# reservoir_level_color.net
KiCad netlist of a schematic drawn in Altium Designer
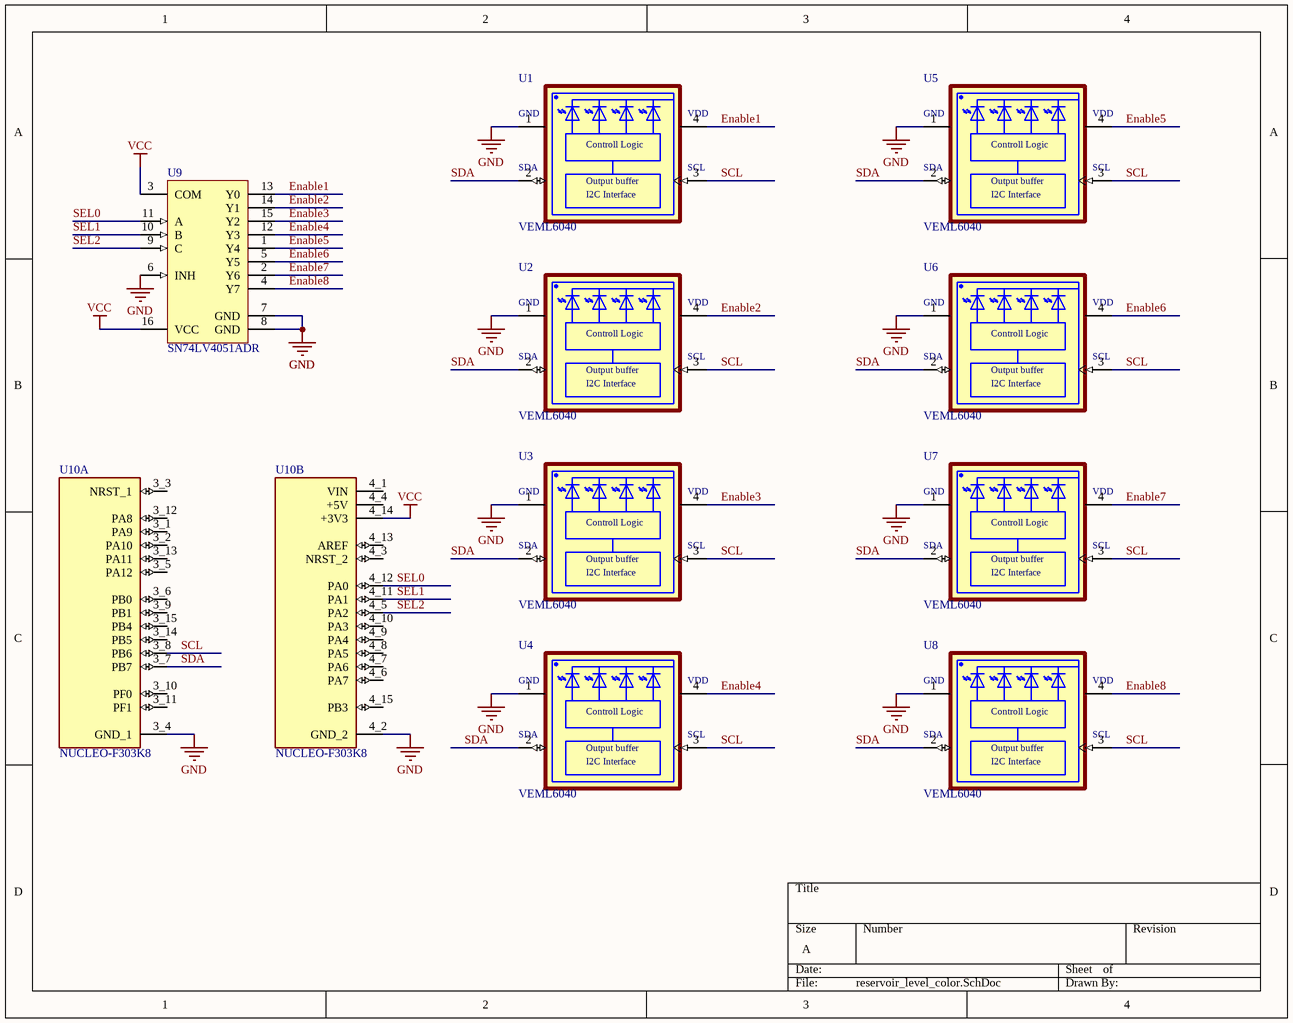
[diagram p0: reservoir_level_color.SchDoc]

(export (version "E")
  (design (tool "Eeschema 10.0.6"))
  (components
    (comp (ref "U1")
      (value "VEML6040")
      (footprint "VEML6040A3OG:VISHAY_VEML6040_1.25X2X1")
      (fields (field (name "MF") "{'manufacturer': u'Vishay'}"))
      (libsource (lib "*") (part "VEML6040"))
    )
    (comp (ref "U2")
      (value "VEML6040")
      (footprint "VEML6040A3OG:VISHAY_VEML6040_1.25X2X1")
      (fields (field (name "MF") "{'manufacturer': u'Vishay'}"))
      (libsource (lib "*") (part "VEML6040"))
    )
    (comp (ref "U3")
      (value "VEML6040")
      (footprint "VEML6040A3OG:VISHAY_VEML6040_1.25X2X1")
      (fields (field (name "MF") "{'manufacturer': u'Vishay'}"))
      (libsource (lib "*") (part "VEML6040"))
    )
    (comp (ref "U4")
      (value "VEML6040")
      (footprint "VEML6040A3OG:VISHAY_VEML6040_1.25X2X1")
      (fields (field (name "MF") "{'manufacturer': u'Vishay'}"))
      (libsource (lib "*") (part "VEML6040"))
    )
    (comp (ref "U5")
      (value "VEML6040")
      (footprint "VEML6040A3OG:VISHAY_VEML6040_1.25X2X1")
      (fields (field (name "MF") "{'manufacturer': u'Vishay'}"))
      (libsource (lib "*") (part "VEML6040"))
    )
    (comp (ref "U6")
      (value "VEML6040")
      (footprint "VEML6040A3OG:VISHAY_VEML6040_1.25X2X1")
      (fields (field (name "MF") "{'manufacturer': u'Vishay'}"))
      (libsource (lib "*") (part "VEML6040"))
    )
    (comp (ref "U7")
      (value "VEML6040")
      (footprint "VEML6040A3OG:VISHAY_VEML6040_1.25X2X1")
      (fields (field (name "MF") "{'manufacturer': u'Vishay'}"))
      (libsource (lib "*") (part "VEML6040"))
    )
    (comp (ref "U8")
      (value "VEML6040")
      (footprint "VEML6040A3OG:VISHAY_VEML6040_1.25X2X1")
      (fields (field (name "MF") "{'manufacturer': u'Vishay'}"))
      (libsource (lib "*") (part "VEML6040"))
    )
    (comp (ref "U9")
      (value "SN74LV4051ADR")
      (footprint "D0016A_M")
      (description "8-Channel Analog Multiplexer/Demultiplexer, D0016A, LARGE T&R")
      (fields
        (field (name "GENERIC PART NUMBER") "SN74LV4051A")
        (field (name "MANUFACTURER") "Texas Instruments")
      )
      (libsource (lib "Altium Content Vault") (part "TI-SN74LV4051A-16"))
    )
    (comp (ref "U10")
      (value "NUCLEO-F303K8")
      (footprint "NUCLEO-F303K8:MODULE_NUCLEO-F303K8")
      (fields (field (name "MF") "{'manufacturer': u'STMicroelectronics'}"))
      (libsource (lib "*") (part "NUCLEO-F303K8"))
    )
  )
  (nets
    (net (code "1") (name "/Enable1") (class "Default")
      (node (ref "U1") (pin "4") (pinfunction "VDD_4") (pintype "power_in"))
      (node (ref "U9") (pin "13") (pinfunction "Y0_13") (pintype "passive"))
    )
    (net (code "2") (name "/Enable2") (class "Default")
      (node (ref "U2") (pin "4") (pinfunction "VDD_4") (pintype "power_in"))
      (node (ref "U9") (pin "14") (pinfunction "Y1_14") (pintype "passive"))
    )
    (net (code "3") (name "/Enable3") (class "Default")
      (node (ref "U3") (pin "4") (pinfunction "VDD_4") (pintype "power_in"))
      (node (ref "U9") (pin "15") (pinfunction "Y2_15") (pintype "passive"))
    )
    (net (code "4") (name "/Enable4") (class "Default")
      (node (ref "U4") (pin "4") (pinfunction "VDD_4") (pintype "power_in"))
      (node (ref "U9") (pin "12") (pinfunction "Y3_12") (pintype "passive"))
    )
    (net (code "5") (name "/Enable5") (class "Default")
      (node (ref "U5") (pin "4") (pinfunction "VDD_4") (pintype "power_in"))
      (node (ref "U9") (pin "1") (pinfunction "Y4_1") (pintype "passive"))
    )
    (net (code "6") (name "/Enable6") (class "Default")
      (node (ref "U6") (pin "4") (pinfunction "VDD_4") (pintype "power_in"))
      (node (ref "U9") (pin "5") (pinfunction "Y5_5") (pintype "passive"))
    )
    (net (code "7") (name "/Enable7") (class "Default")
      (node (ref "U7") (pin "4") (pinfunction "VDD_4") (pintype "power_in"))
      (node (ref "U9") (pin "2") (pinfunction "Y6_2") (pintype "passive"))
    )
    (net (code "8") (name "/Enable8") (class "Default")
      (node (ref "U8") (pin "4") (pinfunction "VDD_4") (pintype "power_in"))
      (node (ref "U9") (pin "4") (pinfunction "Y7_4") (pintype "passive"))
    )
    (net (code "9") (name "/SCL") (class "Default")
      (node (ref "U1") (pin "3") (pinfunction "SCL_3") (pintype "input"))
      (node (ref "U10") (pin "3_8") (pinfunction "PB6_3_8") (pintype "bidirectional"))
      (node (ref "U2") (pin "3") (pinfunction "SCL_3") (pintype "input"))
      (node (ref "U3") (pin "3") (pinfunction "SCL_3") (pintype "input"))
      (node (ref "U4") (pin "3") (pinfunction "SCL_3") (pintype "input"))
      (node (ref "U5") (pin "3") (pinfunction "SCL_3") (pintype "input"))
      (node (ref "U6") (pin "3") (pinfunction "SCL_3") (pintype "input"))
      (node (ref "U7") (pin "3") (pinfunction "SCL_3") (pintype "input"))
      (node (ref "U8") (pin "3") (pinfunction "SCL_3") (pintype "input"))
    )
    (net (code "10") (name "/SDA") (class "Default")
      (node (ref "U1") (pin "2") (pinfunction "SDA_2") (pintype "bidirectional"))
      (node (ref "U10") (pin "3_7") (pinfunction "PB7_3_7") (pintype "bidirectional"))
      (node (ref "U2") (pin "2") (pinfunction "SDA_2") (pintype "bidirectional"))
      (node (ref "U3") (pin "2") (pinfunction "SDA_2") (pintype "bidirectional"))
      (node (ref "U4") (pin "2") (pinfunction "SDA_2") (pintype "bidirectional"))
      (node (ref "U5") (pin "2") (pinfunction "SDA_2") (pintype "bidirectional"))
      (node (ref "U6") (pin "2") (pinfunction "SDA_2") (pintype "bidirectional"))
      (node (ref "U7") (pin "2") (pinfunction "SDA_2") (pintype "bidirectional"))
      (node (ref "U8") (pin "2") (pinfunction "SDA_2") (pintype "bidirectional"))
    )
    (net (code "11") (name "/SEL0") (class "Default")
      (node (ref "U10") (pin "4_12") (pinfunction "PA0_4_12") (pintype "bidirectional"))
      (node (ref "U9") (pin "11") (pinfunction "A_11") (pintype "input"))
    )
    (net (code "12") (name "/SEL1") (class "Default")
      (node (ref "U10") (pin "4_11") (pinfunction "PA1_4_11") (pintype "bidirectional"))
      (node (ref "U9") (pin "10") (pinfunction "B_10") (pintype "input"))
    )
    (net (code "13") (name "/SEL2") (class "Default")
      (node (ref "U10") (pin "4_5") (pinfunction "PA2_4_5") (pintype "bidirectional"))
      (node (ref "U9") (pin "9") (pinfunction "C_9") (pintype "input"))
    )
    (net (code "14") (name "GND") (class "Default")
      (node (ref "U1") (pin "1") (pinfunction "GND_1") (pintype "power_in"))
      (node (ref "U10") (pin "3_4") (pinfunction "GND_1_3_4") (pintype "power_in"))
      (node (ref "U10") (pin "4_2") (pinfunction "GND_2_4_2") (pintype "power_in"))
      (node (ref "U2") (pin "1") (pinfunction "GND_1") (pintype "power_in"))
      (node (ref "U3") (pin "1") (pinfunction "GND_1") (pintype "power_in"))
      (node (ref "U4") (pin "1") (pinfunction "GND_1") (pintype "power_in"))
      (node (ref "U5") (pin "1") (pinfunction "GND_1") (pintype "power_in"))
      (node (ref "U6") (pin "1") (pinfunction "GND_1") (pintype "power_in"))
      (node (ref "U7") (pin "1") (pinfunction "GND_1") (pintype "power_in"))
      (node (ref "U8") (pin "1") (pinfunction "GND_1") (pintype "power_in"))
      (node (ref "U9") (pin "6") (pinfunction "INH_6") (pintype "input"))
      (node (ref "U9") (pin "7") (pinfunction "GND_7") (pintype "power_in"))
      (node (ref "U9") (pin "8") (pinfunction "GND_8") (pintype "power_in"))
    )
    (net (code "15") (name "VCC") (class "Default")
      (node (ref "U10") (pin "4_14") (pinfunction "+3V3_4_14") (pintype "power_in"))
      (node (ref "U9") (pin "16") (pinfunction "VCC_16") (pintype "power_in"))
      (node (ref "U9") (pin "3") (pinfunction "COM_3") (pintype "passive"))
    )
    (net (code "16") (name "unconnected-(U10A-NRST_1-Pad3_3)") (class "Default")
      (node (ref "U10") (pin "3_3") (pinfunction "NRST_1_3_3") (pintype "bidirectional"))
    )
    (net (code "17") (name "unconnected-(U10A-PA8-Pad3_12)") (class "Default")
      (node (ref "U10") (pin "3_12") (pinfunction "PA8_3_12") (pintype "bidirectional"))
    )
    (net (code "18") (name "unconnected-(U10A-PA9-Pad3_1)") (class "Default")
      (node (ref "U10") (pin "3_1") (pinfunction "PA9_3_1") (pintype "bidirectional"))
    )
    (net (code "19") (name "unconnected-(U10A-PA10-Pad3_2)") (class "Default")
      (node (ref "U10") (pin "3_2") (pinfunction "PA10_3_2") (pintype "bidirectional"))
    )
    (net (code "20") (name "unconnected-(U10A-PA11-Pad3_13)") (class "Default")
      (node (ref "U10") (pin "3_13") (pinfunction "PA11_3_13") (pintype "bidirectional"))
    )
    (net (code "21") (name "unconnected-(U10A-PA12-Pad3_5)") (class "Default")
      (node (ref "U10") (pin "3_5") (pinfunction "PA12_3_5") (pintype "bidirectional"))
    )
    (net (code "22") (name "unconnected-(U10A-PB0-Pad3_6)") (class "Default")
      (node (ref "U10") (pin "3_6") (pinfunction "PB0_3_6") (pintype "bidirectional"))
    )
    (net (code "23") (name "unconnected-(U10A-PB1-Pad3_9)") (class "Default")
      (node (ref "U10") (pin "3_9") (pinfunction "PB1_3_9") (pintype "bidirectional"))
    )
    (net (code "24") (name "unconnected-(U10A-PB4-Pad3_15)") (class "Default")
      (node (ref "U10") (pin "3_15") (pinfunction "PB4_3_15") (pintype "bidirectional"))
    )
    (net (code "25") (name "unconnected-(U10A-PB5-Pad3_14)") (class "Default")
      (node (ref "U10") (pin "3_14") (pinfunction "PB5_3_14") (pintype "bidirectional"))
    )
    (net (code "26") (name "unconnected-(U10A-PF0-Pad3_10)") (class "Default")
      (node (ref "U10") (pin "3_10") (pinfunction "PF0_3_10") (pintype "bidirectional"))
    )
    (net (code "27") (name "unconnected-(U10A-PF1-Pad3_11)") (class "Default")
      (node (ref "U10") (pin "3_11") (pinfunction "PF1_3_11") (pintype "bidirectional"))
    )
    (net (code "28") (name "unconnected-(U10B-+5V-Pad4_4)") (class "Default")
      (node (ref "U10") (pin "4_4") (pinfunction "+5V_4_4") (pintype "power_in"))
    )
    (net (code "29") (name "unconnected-(U10B-AREF-Pad4_13)") (class "Default")
      (node (ref "U10") (pin "4_13") (pinfunction "AREF_4_13") (pintype "bidirectional"))
    )
    (net (code "30") (name "unconnected-(U10B-NRST_2-Pad4_3)") (class "Default")
      (node (ref "U10") (pin "4_3") (pinfunction "NRST_2_4_3") (pintype "bidirectional"))
    )
    (net (code "31") (name "unconnected-(U10B-PA3-Pad4_10)") (class "Default")
      (node (ref "U10") (pin "4_10") (pinfunction "PA3_4_10") (pintype "bidirectional"))
    )
    (net (code "32") (name "unconnected-(U10B-PA4-Pad4_9)") (class "Default")
      (node (ref "U10") (pin "4_9") (pinfunction "PA4_4_9") (pintype "bidirectional"))
    )
    (net (code "33") (name "unconnected-(U10B-PA5-Pad4_8)") (class "Default")
      (node (ref "U10") (pin "4_8") (pinfunction "PA5_4_8") (pintype "bidirectional"))
    )
    (net (code "34") (name "unconnected-(U10B-PA6-Pad4_7)") (class "Default")
      (node (ref "U10") (pin "4_7") (pinfunction "PA6_4_7") (pintype "bidirectional"))
    )
    (net (code "35") (name "unconnected-(U10B-PA7-Pad4_6)") (class "Default")
      (node (ref "U10") (pin "4_6") (pinfunction "PA7_4_6") (pintype "bidirectional"))
    )
    (net (code "36") (name "unconnected-(U10B-PB3-Pad4_15)") (class "Default")
      (node (ref "U10") (pin "4_15") (pinfunction "PB3_4_15") (pintype "bidirectional"))
    )
    (net (code "37") (name "unconnected-(U10B-VIN-Pad4_1)") (class "Default")
      (node (ref "U10") (pin "4_1") (pinfunction "VIN_4_1") (pintype "power_in"))
    )
  )
)
